# TMC2130.net
KiCad netlist of a schematic drawn in Altium Designer
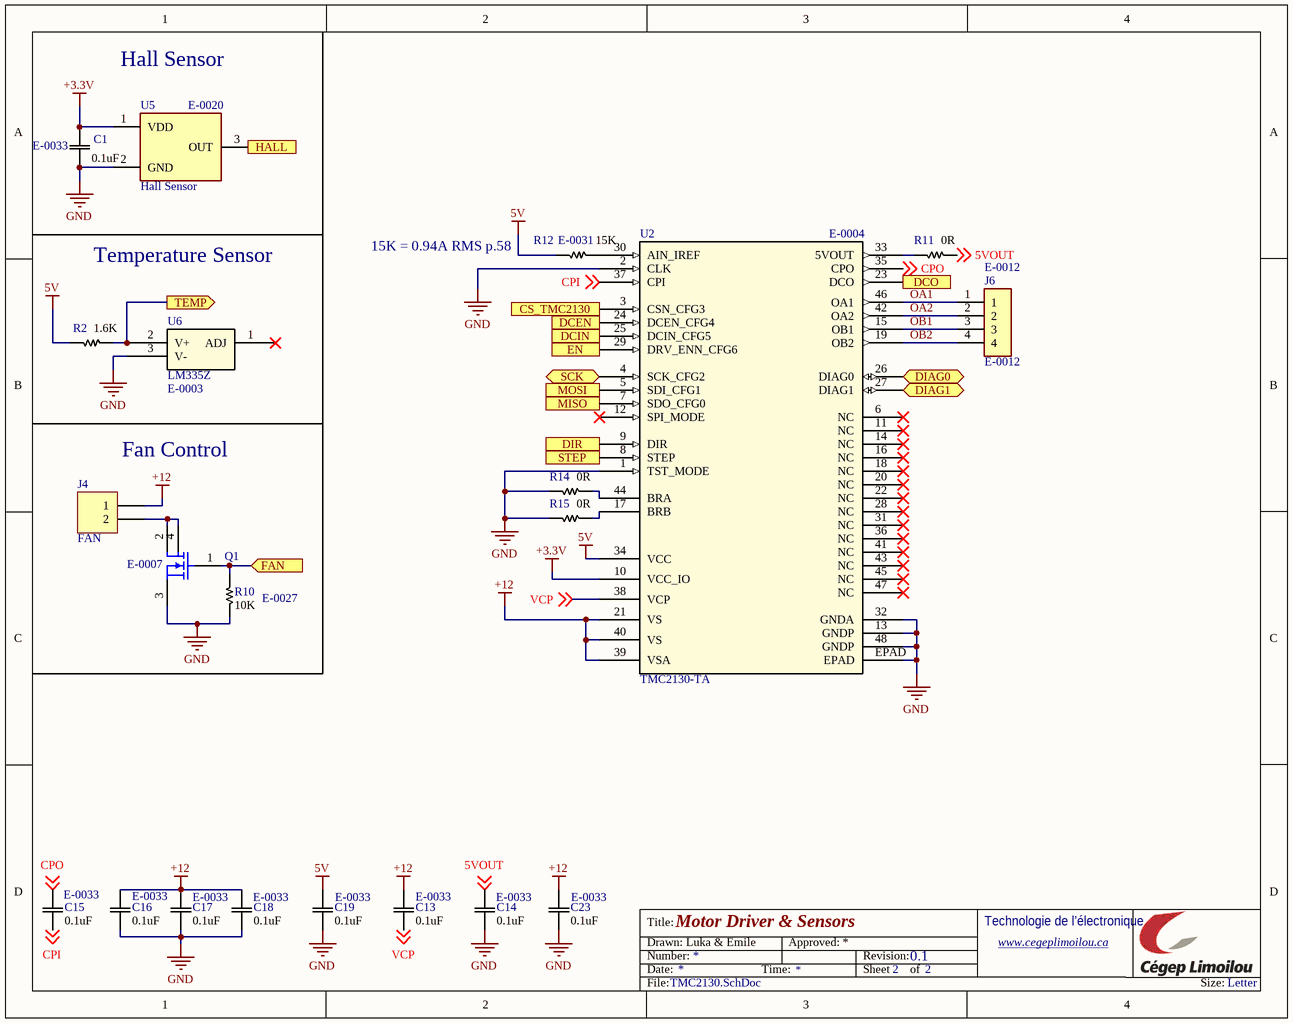
[diagram p0: TMC2130.SchDoc]

(export (version "E")
  (design (tool "Eeschema 10.0.6"))
  (components
    (comp (ref "C1")
      (value "0.1uF")
      (footprint "0603")
      (description "0.1uF Capacitor 0603 SMD")
      (fields
        (field (name "MANUFACTURER_PART_NUMBER") "C0603C104Z3VACTU")
        (field (name "EXCEL NUMBER") "E-0033")
        (field (name "Comment") "E-0033")
        (field (name "COPYRIGHT") "Luka & Émile")
      )
      (libsource (lib "Motor Driver") (part "E-0033"))
    )
    (comp (ref "C13")
      (value "0.1uF")
      (footprint "0603")
      (description "0.1uF Capacitor 0603 SMD")
      (fields
        (field (name "MANUFACTURER_PART_NUMBER") "C0603C104Z3VACTU")
        (field (name "EXCEL NUMBER") "E-0033")
        (field (name "Comment") "E-0033")
        (field (name "COPYRIGHT") "Luka & Émile")
      )
      (libsource (lib "Motor Driver") (part "E-0033"))
    )
    (comp (ref "C14")
      (value "0.1uF")
      (footprint "0603")
      (description "0.1uF Capacitor 0603 SMD")
      (fields
        (field (name "MANUFACTURER_PART_NUMBER") "C0603C104Z3VACTU")
        (field (name "EXCEL NUMBER") "E-0033")
        (field (name "Comment") "E-0033")
        (field (name "COPYRIGHT") "Luka & Émile")
      )
      (libsource (lib "Motor Driver") (part "E-0033"))
    )
    (comp (ref "C15")
      (value "0.1uF")
      (footprint "0603")
      (description "0.1uF Capacitor 0603 SMD")
      (fields
        (field (name "MANUFACTURER_PART_NUMBER") "C0603C104Z3VACTU")
        (field (name "EXCEL NUMBER") "E-0033")
        (field (name "Comment") "E-0033")
        (field (name "COPYRIGHT") "Luka & Émile")
      )
      (libsource (lib "Motor Driver") (part "E-0033"))
    )
    (comp (ref "C16")
      (value "0.1uF")
      (footprint "0603")
      (description "0.1uF Capacitor 0603 SMD")
      (fields
        (field (name "MANUFACTURER_PART_NUMBER") "C0603C104Z3VACTU")
        (field (name "EXCEL NUMBER") "E-0033")
        (field (name "Comment") "E-0033")
        (field (name "COPYRIGHT") "Luka & Émile")
      )
      (libsource (lib "Motor Driver") (part "E-0033"))
    )
    (comp (ref "C17")
      (value "0.1uF")
      (footprint "0603")
      (description "0.1uF Capacitor 0603 SMD")
      (fields
        (field (name "MANUFACTURER_PART_NUMBER") "C0603C104Z3VACTU")
        (field (name "EXCEL NUMBER") "E-0033")
        (field (name "Comment") "E-0033")
        (field (name "COPYRIGHT") "Luka & Émile")
      )
      (libsource (lib "Motor Driver") (part "E-0033"))
    )
    (comp (ref "C18")
      (value "0.1uF")
      (footprint "0603")
      (description "0.1uF Capacitor 0603 SMD")
      (fields
        (field (name "MANUFACTURER_PART_NUMBER") "C0603C104Z3VACTU")
        (field (name "EXCEL NUMBER") "E-0033")
        (field (name "Comment") "E-0033")
        (field (name "COPYRIGHT") "Luka & Émile")
      )
      (libsource (lib "Motor Driver") (part "E-0033"))
    )
    (comp (ref "C19")
      (value "0.1uF")
      (footprint "0603")
      (description "0.1uF Capacitor 0603 SMD")
      (fields
        (field (name "MANUFACTURER_PART_NUMBER") "C0603C104Z3VACTU")
        (field (name "EXCEL NUMBER") "E-0033")
        (field (name "Comment") "E-0033")
        (field (name "COPYRIGHT") "Luka & Émile")
      )
      (libsource (lib "Motor Driver") (part "E-0033"))
    )
    (comp (ref "C23")
      (value "0.1uF")
      (footprint "0603")
      (description "0.1uF Capacitor 0603 SMD")
      (fields
        (field (name "MANUFACTURER_PART_NUMBER") "C0603C104Z3VACTU")
        (field (name "EXCEL NUMBER") "E-0033")
        (field (name "Comment") "E-0033")
        (field (name "COPYRIGHT") "Luka & Émile")
      )
      (libsource (lib "Motor Driver") (part "E-0033"))
    )
    (comp (ref "J4")
      (value "FAN")
      (footprint "HDR1X2")
      (description "Header, 2-Pin")
      (fields
        (field (name "MANUFACTURER_PART_NUMBER") "61300411121")
        (field (name "COPYRIGHT") "Luka & Émile")
      )
      (libsource (lib "Motor Driver") (part "E-0047"))
    )
    (comp (ref "J6")
      (value "E-0012")
      (footprint "JST 4POS 2.5mm 90°")
      (description "Connector JST 4POS")
      (fields
        (field (name "MANUFACTURER_PART_NUMBER") "S4B-XH-A(LF)(SN)")
        (field (name "EXCEL NUMBER") "E-0012")
        (field (name "COPYRIGHT") "Luka & Émile")
      )
      (libsource (lib "Motor Driver") (part "E-0012"))
    )
    (comp (ref "Q1")
      (value "E-0007")
      (footprint "SOT223_M")
      (description "55V 7A SOT223")
      (fields
        (field (name "EXCEL NUMBER") "E-0007")
        (field (name "MANUFACTURER_PART_NUMBER") "BUK9880-55A/CUX")
        (field (name "COPYRIGHT") "Luka & Émile")
      )
      (libsource (lib "Motor Driver") (part "E-0007"))
    )
    (comp (ref "R2")
      (value "1.6K")
      (footprint "0603")
      (description "1.6K Resistor 0603 SMD")
      (fields
        (field (name "MANUFACTURER_PART_NUMBER") "CRCW06031K60JNEA")
        (field (name "Comment") "E-0050")
        (field (name "COPYRIGHT") "Luka & Émile")
      )
      (libsource (lib "Motor Driver") (part "E-0050"))
    )
    (comp (ref "R10")
      (value "10K")
      (footprint "0603")
      (description "10K Resistor 0603 SMD")
      (fields
        (field (name "MANUFACTURER_PART_NUMBER") "RMCF0603JT10K0")
        (field (name "EXCEL NUMBER") "E-0027")
        (field (name "Comment") "Resistor 0603")
        (field (name "COPYRIGHT") "Luka & Émile")
      )
      (libsource (lib "Motor Driver") (part "E-0027"))
    )
    (comp (ref "R11")
      (value "0R")
      (footprint "0603")
      (description "Jumper 0603")
      (fields (field (name "Comment") "Jumper") (field (name "COPYRIGHT") "Luka & Émile"))
      (libsource (lib "Motor Driver") (part "Jumper"))
    )
    (comp (ref "R12")
      (value "15K")
      (footprint "0603")
      (description "15K Resistor 0603 SMD")
      (fields
        (field (name "MANUFACTURER_PART_NUMBER") "RMCF0603FG15K0")
        (field (name "EXCEL NUMBER") "E-0031")
        (field (name "Comment") "E-0031")
        (field (name "COPYRIGHT") "Luka & Émile")
      )
      (libsource (lib "Motor Driver") (part "E-0031"))
    )
    (comp (ref "R14")
      (value "0R")
      (footprint "0603")
      (description "Jumper 0603")
      (fields (field (name "Comment") "Jumper") (field (name "COPYRIGHT") "Luka & Émile"))
      (libsource (lib "Motor Driver") (part "Jumper"))
    )
    (comp (ref "R15")
      (value "0R")
      (footprint "0603")
      (description "Jumper 0603")
      (fields (field (name "Comment") "Jumper") (field (name "COPYRIGHT") "Luka & Émile"))
      (libsource (lib "Motor Driver") (part "Jumper"))
    )
    (comp (ref "U2")
      (value "TMC2130-TA")
      (footprint "eTQFP48_9x9")
      (description "Motor Driver TMC2130-TA")
      (fields
        (field (name "MANUFACTURER_PART_NUMBER") "TMC2130-TA-T")
        (field (name "EXCEL NUMBER") "E-0004")
        (field (name "COPYRIGHT") "Luka & Émile")
      )
      (libsource (lib "Motor Driver") (part "E-0004"))
    )
    (comp (ref "U5")
      (value "Hall Sensor")
      (footprint "Footprint_Emile:AH372PB")
      (fields
        (field (name "MANUFACTURER_PART_NUMBER") "AH372-P-B")
        (field (name "EXCEL NUMBER") "E-0020")
        (field (name "COPYRIGHT") "Luka & Émile")
      )
      (libsource (lib "Motor Driver") (part "E-0020"))
    )
    (comp (ref "U6")
      (value "LM335Z")
      (footprint "TO92")
      (description "Temperature Sensor LM335Z")
      (fields (field (name "EXCEL NUMBER") "E-0003") (field (name "COPYRIGHT") "Luka & Émile"))
      (libsource (lib "Motor Driver") (part "E-0003"))
    )
  )
  (nets
    (net (code "1") (name "+3.3V") (class "Default")
      (node (ref "C1") (pin "2") (pinfunction "2_2") (pintype "passive"))
      (node (ref "U2") (pin "10") (pinfunction "VCC_IO_10") (pintype "power_in"))
      (node (ref "U5") (pin "1") (pinfunction "VDD_1") (pintype "passive"))
    )
    (net (code "2") (name "+12") (class "Default")
      (node (ref "C13") (pin "2") (pinfunction "2_2") (pintype "passive"))
      (node (ref "C16") (pin "2") (pinfunction "2_2") (pintype "passive"))
      (node (ref "C17") (pin "2") (pinfunction "2_2") (pintype "passive"))
      (node (ref "C18") (pin "2") (pinfunction "2_2") (pintype "passive"))
      (node (ref "C23") (pin "2") (pinfunction "2_2") (pintype "passive"))
      (node (ref "J4") (pin "1") (pinfunction "1_1") (pintype "passive"))
      (node (ref "U2") (pin "21") (pinfunction "VS_21") (pintype "power_in"))
      (node (ref "U2") (pin "39") (pinfunction "VSA_39") (pintype "power_in"))
      (node (ref "U2") (pin "40") (pinfunction "VS_40") (pintype "power_in"))
    )
    (net (code "3") (name "/CS_TMC2130") (class "Default")
      (node (ref "U2") (pin "3") (pinfunction "CSN_CFG3_3") (pintype "input"))
    )
    (net (code "4") (name "/DCEN") (class "Default")
      (node (ref "U2") (pin "24") (pinfunction "DCEN_CFG4_24") (pintype "input"))
    )
    (net (code "5") (name "/DCIN") (class "Default")
      (node (ref "U2") (pin "25") (pinfunction "DCIN_CFG5_25") (pintype "input"))
    )
    (net (code "6") (name "/DCO") (class "Default")
      (node (ref "U2") (pin "23") (pinfunction "DCO_23") (pintype "output"))
    )
    (net (code "7") (name "/DIAG0") (class "Default")
      (node (ref "U2") (pin "26") (pinfunction "DIAG0_26") (pintype "bidirectional"))
    )
    (net (code "8") (name "/DIAG1") (class "Default")
      (node (ref "U2") (pin "27") (pinfunction "DIAG1_27") (pintype "bidirectional"))
    )
    (net (code "9") (name "/DIR") (class "Default")
      (node (ref "U2") (pin "9") (pinfunction "DIR_9") (pintype "input"))
    )
    (net (code "10") (name "/EN") (class "Default")
      (node (ref "U2") (pin "29") (pinfunction "DRV_ENN_CFG6_29") (pintype "input"))
    )
    (net (code "11") (name "/FAN") (class "Default")
      (node (ref "Q1") (pin "1") (pinfunction "G_1") (pintype "passive"))
      (node (ref "R10") (pin "2") (pinfunction "2_2") (pintype "passive"))
    )
    (net (code "12") (name "/HALL") (class "Default")
      (node (ref "U5") (pin "3") (pinfunction "OUT_3") (pintype "passive"))
    )
    (net (code "13") (name "/MISO") (class "Default")
      (node (ref "U2") (pin "7") (pinfunction "SDO_CFG0_7") (pintype "input"))
    )
    (net (code "14") (name "/MOSI") (class "Default")
      (node (ref "U2") (pin "5") (pinfunction "SDI_CFG1_5") (pintype "input"))
    )
    (net (code "15") (name "/OA1") (class "Default")
      (node (ref "J6") (pin "1") (pinfunction "1_1") (pintype "passive"))
      (node (ref "U2") (pin "46") (pinfunction "OA1_46") (pintype "output"))
    )
    (net (code "16") (name "/OA2") (class "Default")
      (node (ref "J6") (pin "2") (pinfunction "2_2") (pintype "passive"))
      (node (ref "U2") (pin "42") (pinfunction "OA2_42") (pintype "output"))
    )
    (net (code "17") (name "/OB1") (class "Default")
      (node (ref "J6") (pin "3") (pinfunction "3_3") (pintype "passive"))
      (node (ref "U2") (pin "15") (pinfunction "OB1_15") (pintype "output"))
    )
    (net (code "18") (name "/OB2") (class "Default")
      (node (ref "J6") (pin "4") (pinfunction "4_4") (pintype "passive"))
      (node (ref "U2") (pin "19") (pinfunction "OB2_19") (pintype "output"))
    )
    (net (code "19") (name "/SCK") (class "Default")
      (node (ref "U2") (pin "4") (pinfunction "SCK_CFG2_4") (pintype "input"))
    )
    (net (code "20") (name "/STEP") (class "Default")
      (node (ref "U2") (pin "8") (pinfunction "STEP_8") (pintype "input"))
    )
    (net (code "21") (name "/TEMP") (class "Default")
      (node (ref "R2") (pin "2") (pinfunction "2_2") (pintype "passive"))
      (node (ref "U6") (pin "2") (pinfunction "V+_2") (pintype "power_in"))
    )
    (net (code "22") (name "5V") (class "Default")
      (node (ref "C19") (pin "2") (pinfunction "2_2") (pintype "passive"))
      (node (ref "R12") (pin "1") (pinfunction "1_1") (pintype "passive"))
      (node (ref "R2") (pin "1") (pinfunction "1_1") (pintype "passive"))
      (node (ref "U2") (pin "34") (pinfunction "VCC_34") (pintype "power_in"))
    )
    (net (code "23") (name "5VOUT") (class "Default")
      (node (ref "C14") (pin "2") (pinfunction "2_2") (pintype "passive"))
      (node (ref "R11") (pin "2") (pinfunction "2_2") (pintype "passive"))
    )
    (net (code "24") (name "CPI") (class "Default")
      (node (ref "C15") (pin "1") (pinfunction "1_1") (pintype "passive"))
      (node (ref "U2") (pin "37") (pinfunction "CPI_37") (pintype "input"))
    )
    (net (code "25") (name "CPO") (class "Default")
      (node (ref "C15") (pin "2") (pinfunction "2_2") (pintype "passive"))
      (node (ref "U2") (pin "35") (pinfunction "CPO_35") (pintype "output"))
    )
    (net (code "26") (name "GND") (class "Default")
      (node (ref "C1") (pin "1") (pinfunction "1_1") (pintype "passive"))
      (node (ref "C14") (pin "1") (pinfunction "1_1") (pintype "passive"))
      (node (ref "C16") (pin "1") (pinfunction "1_1") (pintype "passive"))
      (node (ref "C17") (pin "1") (pinfunction "1_1") (pintype "passive"))
      (node (ref "C18") (pin "1") (pinfunction "1_1") (pintype "passive"))
      (node (ref "C19") (pin "1") (pinfunction "1_1") (pintype "passive"))
      (node (ref "C23") (pin "1") (pinfunction "1_1") (pintype "passive"))
      (node (ref "Q1") (pin "3") (pinfunction "S_3") (pintype "passive"))
      (node (ref "R10") (pin "1") (pinfunction "1_1") (pintype "passive"))
      (node (ref "R14") (pin "1") (pinfunction "1_1") (pintype "passive"))
      (node (ref "R15") (pin "1") (pinfunction "1_1") (pintype "passive"))
      (node (ref "U2") (pin "1") (pinfunction "TST_MODE_1") (pintype "input"))
      (node (ref "U2") (pin "13") (pinfunction "GNDP_13") (pintype "power_in"))
      (node (ref "U2") (pin "2") (pinfunction "CLK_2") (pintype "input"))
      (node (ref "U2") (pin "32") (pinfunction "GNDA_32") (pintype "power_in"))
      (node (ref "U2") (pin "48") (pinfunction "GNDP_48") (pintype "power_in"))
      (node (ref "U2") (pin "EPAD") (pinfunction "EPAD_EPAD") (pintype "passive"))
      (node (ref "U5") (pin "2") (pinfunction "GND_2") (pintype "passive"))
      (node (ref "U6") (pin "3") (pinfunction "V-_3") (pintype "power_in"))
    )
    (net (code "27") (name "Net-(J4-Pad2)") (class "Default")
      (node (ref "J4") (pin "2") (pinfunction "2_2") (pintype "passive"))
      (node (ref "Q1") (pin "2") (pinfunction "D_2") (pintype "passive"))
      (node (ref "Q1") (pin "4") (pinfunction "D_4") (pintype "passive"))
    )
    (net (code "28") (name "Net-(U2-5VOUT)") (class "Default")
      (node (ref "R11") (pin "1") (pinfunction "1_1") (pintype "passive"))
      (node (ref "U2") (pin "33") (pinfunction "5VOUT_33") (pintype "output"))
    )
    (net (code "29") (name "Net-(U2-AIN_IREF)") (class "Default")
      (node (ref "R12") (pin "2") (pinfunction "2_2") (pintype "passive"))
      (node (ref "U2") (pin "30") (pinfunction "AIN_IREF_30") (pintype "input"))
    )
    (net (code "30") (name "Net-(U2-BRA)") (class "Default")
      (node (ref "R14") (pin "2") (pinfunction "2_2") (pintype "passive"))
      (node (ref "U2") (pin "44") (pinfunction "BRA_44") (pintype "passive"))
    )
    (net (code "31") (name "Net-(U2-BRB)") (class "Default")
      (node (ref "R15") (pin "2") (pinfunction "2_2") (pintype "passive"))
      (node (ref "U2") (pin "17") (pinfunction "BRB_17") (pintype "passive"))
    )
    (net (code "32") (name "VCP") (class "Default")
      (node (ref "C13") (pin "1") (pinfunction "1_1") (pintype "passive"))
      (node (ref "U2") (pin "38") (pinfunction "VCP_38") (pintype "power_in"))
    )
    (net (code "33") (name "unconnected-(U2-NC-Pad6)") (class "Default")
      (node (ref "U2") (pin "6") (pinfunction "NC_6") (pintype "passive+no_connect"))
    )
    (net (code "34") (name "unconnected-(U2-NC-Pad11)") (class "Default")
      (node (ref "U2") (pin "11") (pinfunction "NC_11") (pintype "passive+no_connect"))
    )
    (net (code "35") (name "unconnected-(U2-NC-Pad14)") (class "Default")
      (node (ref "U2") (pin "14") (pinfunction "NC_14") (pintype "passive+no_connect"))
    )
    (net (code "36") (name "unconnected-(U2-NC-Pad16)") (class "Default")
      (node (ref "U2") (pin "16") (pinfunction "NC_16") (pintype "passive+no_connect"))
    )
    (net (code "37") (name "unconnected-(U2-NC-Pad18)") (class "Default")
      (node (ref "U2") (pin "18") (pinfunction "NC_18") (pintype "passive+no_connect"))
    )
    (net (code "38") (name "unconnected-(U2-NC-Pad20)") (class "Default")
      (node (ref "U2") (pin "20") (pinfunction "NC_20") (pintype "passive+no_connect"))
    )
    (net (code "39") (name "unconnected-(U2-NC-Pad22)") (class "Default")
      (node (ref "U2") (pin "22") (pinfunction "NC_22") (pintype "passive+no_connect"))
    )
    (net (code "40") (name "unconnected-(U2-NC-Pad28)") (class "Default")
      (node (ref "U2") (pin "28") (pinfunction "NC_28") (pintype "passive+no_connect"))
    )
    (net (code "41") (name "unconnected-(U2-NC-Pad31)") (class "Default")
      (node (ref "U2") (pin "31") (pinfunction "NC_31") (pintype "passive+no_connect"))
    )
    (net (code "42") (name "unconnected-(U2-NC-Pad36)") (class "Default")
      (node (ref "U2") (pin "36") (pinfunction "NC_36") (pintype "passive+no_connect"))
    )
    (net (code "43") (name "unconnected-(U2-NC-Pad41)") (class "Default")
      (node (ref "U2") (pin "41") (pinfunction "NC_41") (pintype "passive+no_connect"))
    )
    (net (code "44") (name "unconnected-(U2-NC-Pad43)") (class "Default")
      (node (ref "U2") (pin "43") (pinfunction "NC_43") (pintype "passive+no_connect"))
    )
    (net (code "45") (name "unconnected-(U2-NC-Pad45)") (class "Default")
      (node (ref "U2") (pin "45") (pinfunction "NC_45") (pintype "passive+no_connect"))
    )
    (net (code "46") (name "unconnected-(U2-NC-Pad47)") (class "Default")
      (node (ref "U2") (pin "47") (pinfunction "NC_47") (pintype "passive+no_connect"))
    )
    (net (code "47") (name "unconnected-(U2-SPI_MODE-Pad12)") (class "Default")
      (node (ref "U2") (pin "12") (pinfunction "SPI_MODE_12") (pintype "input+no_connect"))
    )
    (net (code "48") (name "unconnected-(U6-ADJ-Pad1)") (class "Default")
      (node (ref "U6") (pin "1") (pinfunction "ADJ_1") (pintype "passive+no_connect"))
    )
  )
)
